# CAN.net
KiCad netlist of a schematic drawn in Altium Designer
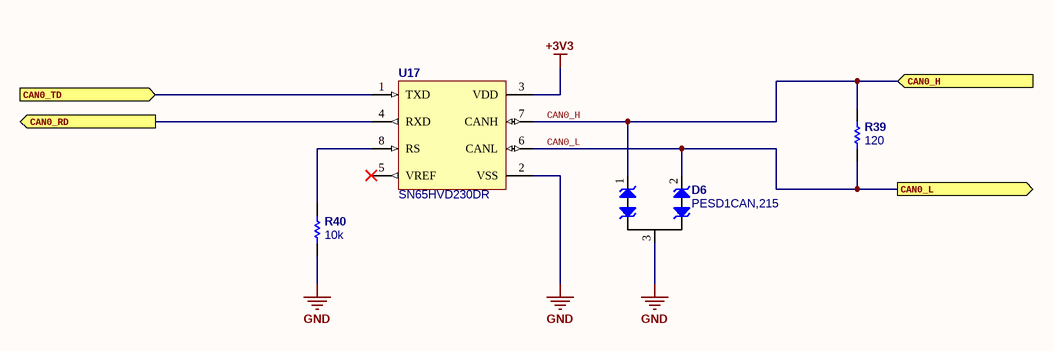
[diagram p0: CAN.SchDoc]

(export (version "E")
  (design (tool "Eeschema 10.0.6"))
  (components
    (comp (ref "D6")
      (value "PESD1CAN,215")
      (footprint "Integrated Circuits SMT-N:SOT23_MEDIUM")
      (description "TVS DIODE 24VWM 70VC SOT23")
      (fields (field (name "MANUFACTURER") "NXP Semiconductors"))
      (libsource (lib "Diodes-N") (part "PESD1CAN,215"))
    )
    (comp (ref "R39")
      (value "120")
      (footprint "R1206_0.70MM_HD")
      (description "RES 120 OHM 1/4W 1% 1206 SMD")
      (fields
        (field (name "MANUFACTURER") "Panasonic Electronic Components")
        (field (name "MANUFACTURER PART NUMBER") "ERJ-8ENF1200V")
      )
      (libsource (lib "Resistors - Panasonic - AEC-Q200") (part "R_2P"))
    )
    (comp (ref "R40")
      (value "10k")
      (footprint "R0603_0.55MM_MD")
      (description "RES 10K OHM 1/10W 1% 0603 SMD")
      (fields
        (field (name "MANUFACTURER") "Panasonic Electronic Components")
        (field (name "MANUFACTURER PART NUMBER") "ERJ-3EKF1002V")
      )
      (libsource (lib "Resistors - Panasonic - AEC-Q200") (part "R_2P"))
    )
    (comp (ref "U17")
      (value "SN65HVD230DR")
      (footprint "Integrated Circuits SMT-N:SOIC-8")
      (description "CAN Interface IC STANDBY MODE")
      (fields (field (name "MANUFACTURER") "Texas Instruments"))
      (libsource (lib "Texas Instruments-N") (part "SN65HVD230DR"))
    )
  )
  (nets
    (net (code "1") (name "+3V3") (class "Default")
      (node (ref "U17") (pin "3") (pinfunction "VDD_3") (pintype "power_in"))
    )
    (net (code "2") (name "/CAN0_H") (class "Default")
      (node (ref "D6") (pin "1") (pinfunction "C1_1") (pintype "passive"))
      (node (ref "R39") (pin "2") (pinfunction "2_2") (pintype "passive"))
      (node (ref "U17") (pin "7") (pinfunction "CANH_7") (pintype "bidirectional"))
    )
    (net (code "3") (name "/CAN0_L") (class "Default")
      (node (ref "D6") (pin "2") (pinfunction "C2_2") (pintype "passive"))
      (node (ref "R39") (pin "1") (pinfunction "1_1") (pintype "passive"))
      (node (ref "U17") (pin "6") (pinfunction "CANL_6") (pintype "bidirectional"))
    )
    (net (code "4") (name "/CAN0_RD") (class "Default")
      (node (ref "U17") (pin "4") (pinfunction "RXD_4") (pintype "output"))
    )
    (net (code "5") (name "/CAN0_TD") (class "Default")
      (node (ref "U17") (pin "1") (pinfunction "TXD_1") (pintype "input"))
    )
    (net (code "6") (name "GND") (class "Default")
      (node (ref "D6") (pin "3") (pinfunction "A_3") (pintype "passive"))
      (node (ref "R40") (pin "1") (pinfunction "1_1") (pintype "passive"))
      (node (ref "U17") (pin "2") (pinfunction "VSS_2") (pintype "power_in"))
    )
    (net (code "7") (name "Net-(U17-RS)") (class "Default")
      (node (ref "R40") (pin "2") (pinfunction "2_2") (pintype "passive"))
      (node (ref "U17") (pin "8") (pinfunction "RS_8") (pintype "input"))
    )
    (net (code "8") (name "unconnected-(U17-VREF-Pad5)") (class "Default")
      (node (ref "U17") (pin "5") (pinfunction "VREF_5") (pintype "output+no_connect"))
    )
  )
)
